# ardusb_zif.net
KiCad netlist of a schematic drawn in EAGLE
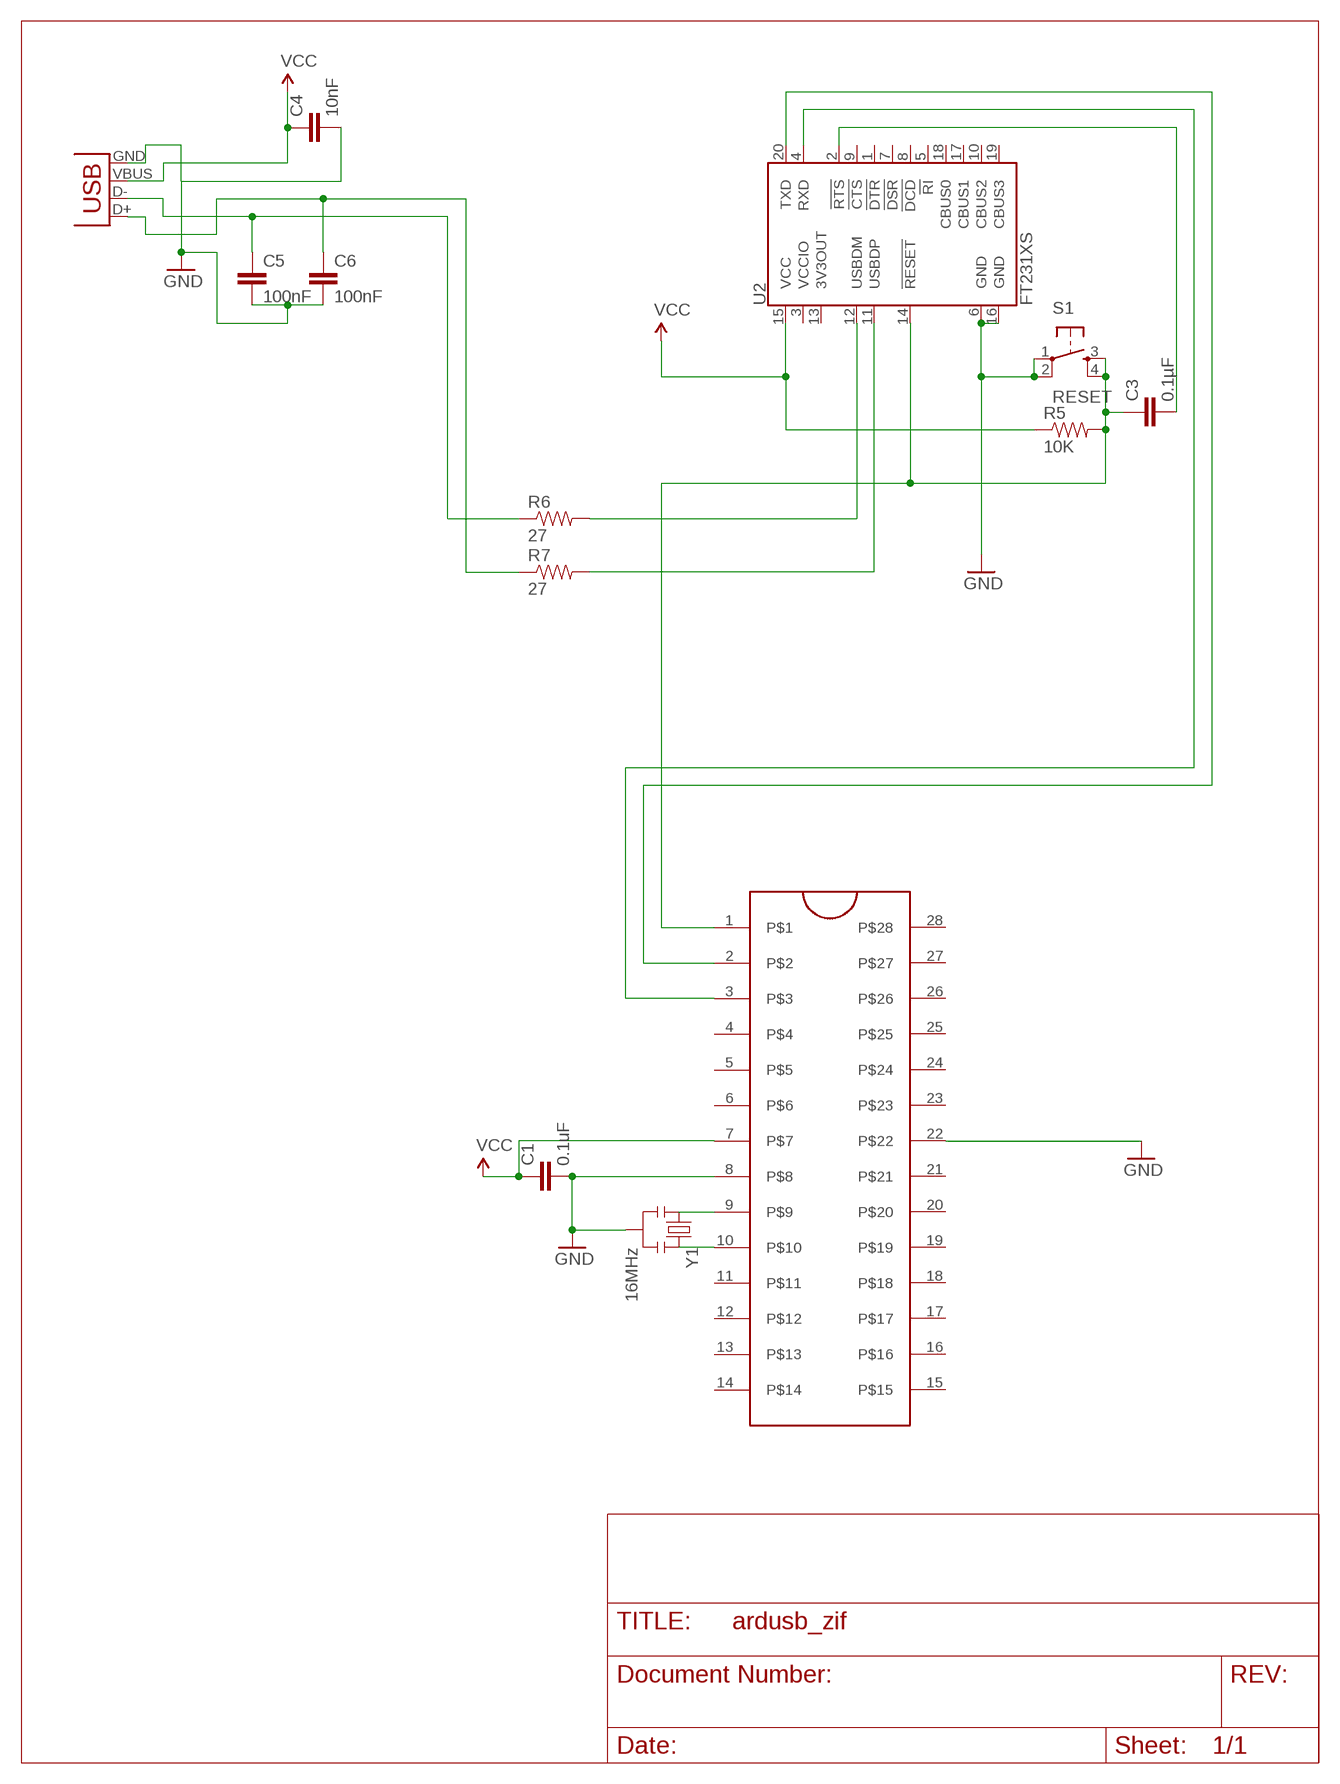
[diagram p0: schematic, sheet 1]

(export (version "E")
  (design (tool "Eeschema 10.0.6"))
  (components
    (comp (ref "C1")
      (value "0.1uF")
      (footprint "eagle-import:CAP-PTH-SMALL")
      (libsource (lib "eagle-import") (part "CAPPTH"))
    )
    (comp (ref "C3")
      (value "0.1µF")
      (footprint "eagle-import:CAP-PTH-SMALL")
      (libsource (lib "eagle-import") (part "SparkFun-Passives_CAPPTH"))
    )
    (comp (ref "C4")
      (value "10nF")
      (footprint "eagle-import:CAP-PTH-SMALL")
      (libsource (lib "eagle-import") (part "SparkFun-Passives_CAPPTH"))
    )
    (comp (ref "C5")
      (value "100nF")
      (footprint "eagle-import:CAP-PTH-SMALL")
      (libsource (lib "eagle-import") (part "CAPPTH"))
    )
    (comp (ref "C6")
      (value "100nF")
      (footprint "eagle-import:CAP-PTH-SMALL")
      (libsource (lib "eagle-import") (part "CAPPTH"))
    )
    (comp (ref "JP1")
      (value "USB-B")
      (footprint "eagle-import:USB-B-PTH")
      (libsource (lib "eagle-import") (part "USBPTH"))
    )
    (comp (ref "R5")
      (value "10K")
      (footprint "eagle-import:AXIAL-0.6")
      (libsource (lib "eagle-import") (part "RESISTORPTH-1W"))
    )
    (comp (ref "R6")
      (value "27")
      (footprint "eagle-import:AXIAL-0.6")
      (libsource (lib "eagle-import") (part "RESISTORPTH-1W"))
    )
    (comp (ref "R7")
      (value "27")
      (footprint "eagle-import:AXIAL-0.6")
      (libsource (lib "eagle-import") (part "RESISTORPTH-1W"))
    )
    (comp (ref "S1")
      (value "RESET")
      (footprint "eagle-import:TACTILE-PTH")
      (libsource (lib "eagle-import") (part "TAC_SWITCHPTH"))
    )
    (comp (ref "U$1")
      (value "ZIFSOCKET-28-3ZIFFSOCKET-28-3")
      (footprint "eagle-import:DIL28-3-ZIF_SOCKET")
      (libsource (lib "eagle-import") (part "ZIFSOCKET-28-3ZIFFSOCKET-28-3"))
    )
    (comp (ref "U2")
      (value "FT231XS")
      (footprint "eagle-import:SSOP20_L")
      (libsource (lib "eagle-import") (part "FT231XS"))
    )
    (comp (ref "Y1")
      (value "16MHz")
      (footprint "eagle-import:RESONATOR-PTH")
      (libsource (lib "eagle-import") (part "RESONATORPTH"))
    )
  )
  (nets
    (net (code "1") (name "GND") (class "Default")
      (node (ref "C1") (pin "2") (pinfunction "2_2") (pintype "passive"))
      (node (ref "C4") (pin "2") (pinfunction "2_2") (pintype "passive"))
      (node (ref "C5") (pin "2") (pinfunction "2_2") (pintype "passive"))
      (node (ref "C6") (pin "2") (pinfunction "2_2") (pintype "passive"))
      (node (ref "JP1") (pin "GND") (pinfunction "GND_GND") (pintype "bidirectional"))
      (node (ref "S1") (pin "1") (pinfunction "1_1") (pintype "passive"))
      (node (ref "S1") (pin "2") (pinfunction "2_2") (pintype "passive"))
      (node (ref "U$1") (pin "22") (pinfunction "P$22_22") (pintype "bidirectional"))
      (node (ref "U$1") (pin "8") (pinfunction "P$8_8") (pintype "bidirectional"))
      (node (ref "U2") (pin "16") (pinfunction "GND_16") (pintype "bidirectional"))
      (node (ref "U2") (pin "6") (pinfunction "GND_6") (pintype "bidirectional"))
      (node (ref "Y1") (pin "2") (pinfunction "2_2") (pintype "passive"))
    )
    (net (code "2") (name "Net-(R5-2)") (class "Default")
      (node (ref "C3") (pin "1") (pinfunction "1_1") (pintype "passive"))
      (node (ref "R5") (pin "P$2") (pinfunction "2_P$2") (pintype "passive"))
      (node (ref "S1") (pin "3") (pinfunction "3_3") (pintype "passive"))
      (node (ref "S1") (pin "4") (pinfunction "4_4") (pintype "passive"))
      (node (ref "U$1") (pin "1") (pinfunction "P$1_1") (pintype "bidirectional"))
      (node (ref "U2") (pin "14") (pinfunction "~{RESET}_14") (pintype "bidirectional"))
    )
    (net (code "3") (name "Net-(R6-1)") (class "Default")
      (node (ref "C5") (pin "1") (pinfunction "1_1") (pintype "passive"))
      (node (ref "JP1") (pin "D-") (pinfunction "D-_D-") (pintype "bidirectional"))
      (node (ref "R6") (pin "P$1") (pinfunction "1_P$1") (pintype "passive"))
    )
    (net (code "4") (name "Net-(R6-2)") (class "Default")
      (node (ref "R6") (pin "P$2") (pinfunction "2_P$2") (pintype "passive"))
      (node (ref "U2") (pin "12") (pinfunction "USBDM_12") (pintype "bidirectional"))
    )
    (net (code "5") (name "Net-(R7-1)") (class "Default")
      (node (ref "C6") (pin "1") (pinfunction "1_1") (pintype "passive"))
      (node (ref "JP1") (pin "D+") (pinfunction "D+_D+") (pintype "bidirectional"))
      (node (ref "R7") (pin "P$1") (pinfunction "1_P$1") (pintype "passive"))
    )
    (net (code "6") (name "Net-(R7-2)") (class "Default")
      (node (ref "R7") (pin "P$2") (pinfunction "2_P$2") (pintype "passive"))
      (node (ref "U2") (pin "11") (pinfunction "USBDP_11") (pintype "bidirectional"))
    )
    (net (code "7") (name "Net-(U$1-P$2)") (class "Default")
      (node (ref "U$1") (pin "2") (pinfunction "P$2_2") (pintype "bidirectional"))
      (node (ref "U2") (pin "20") (pinfunction "TXD_20") (pintype "bidirectional"))
    )
    (net (code "8") (name "Net-(U$1-P$3)") (class "Default")
      (node (ref "U$1") (pin "3") (pinfunction "P$3_3") (pintype "bidirectional"))
      (node (ref "U2") (pin "4") (pinfunction "RXD_4") (pintype "bidirectional"))
    )
    (net (code "9") (name "Net-(U$1-P$9)") (class "Default")
      (node (ref "U$1") (pin "9") (pinfunction "P$9_9") (pintype "bidirectional"))
      (node (ref "Y1") (pin "1") (pinfunction "1_1") (pintype "passive"))
    )
    (net (code "10") (name "Net-(U$1-P$10)") (class "Default")
      (node (ref "U$1") (pin "10") (pinfunction "P$10_10") (pintype "bidirectional"))
      (node (ref "Y1") (pin "3") (pinfunction "3_3") (pintype "passive"))
    )
    (net (code "11") (name "Net-(U2-~{RTS})") (class "Default")
      (node (ref "C3") (pin "2") (pinfunction "2_2") (pintype "passive"))
      (node (ref "U2") (pin "2") (pinfunction "~{RTS}_2") (pintype "bidirectional"))
    )
    (net (code "12") (name "VCC") (class "Default")
      (node (ref "C1") (pin "1") (pinfunction "1_1") (pintype "passive"))
      (node (ref "C4") (pin "1") (pinfunction "1_1") (pintype "passive"))
      (node (ref "JP1") (pin "VBUS") (pinfunction "VBUS_VBUS") (pintype "bidirectional"))
      (node (ref "R5") (pin "P$1") (pinfunction "1_P$1") (pintype "passive"))
      (node (ref "U$1") (pin "7") (pinfunction "P$7_7") (pintype "bidirectional"))
      (node (ref "U2") (pin "15") (pinfunction "VCC_15") (pintype "bidirectional"))
    )
    (net (code "13") (name "unconnected-(U$1-P$4-Pad4)") (class "Default")
      (node (ref "U$1") (pin "4") (pinfunction "P$4_4") (pintype "bidirectional"))
    )
    (net (code "14") (name "unconnected-(U$1-P$5-Pad5)") (class "Default")
      (node (ref "U$1") (pin "5") (pinfunction "P$5_5") (pintype "bidirectional"))
    )
    (net (code "15") (name "unconnected-(U$1-P$6-Pad6)") (class "Default")
      (node (ref "U$1") (pin "6") (pinfunction "P$6_6") (pintype "bidirectional"))
    )
    (net (code "16") (name "unconnected-(U$1-P$11-Pad11)") (class "Default")
      (node (ref "U$1") (pin "11") (pinfunction "P$11_11") (pintype "bidirectional"))
    )
    (net (code "17") (name "unconnected-(U$1-P$12-Pad12)") (class "Default")
      (node (ref "U$1") (pin "12") (pinfunction "P$12_12") (pintype "bidirectional"))
    )
    (net (code "18") (name "unconnected-(U$1-P$13-Pad13)") (class "Default")
      (node (ref "U$1") (pin "13") (pinfunction "P$13_13") (pintype "bidirectional"))
    )
    (net (code "19") (name "unconnected-(U$1-P$14-Pad14)") (class "Default")
      (node (ref "U$1") (pin "14") (pinfunction "P$14_14") (pintype "bidirectional"))
    )
    (net (code "20") (name "unconnected-(U$1-P$15-Pad15)") (class "Default")
      (node (ref "U$1") (pin "15") (pinfunction "P$15_15") (pintype "bidirectional"))
    )
    (net (code "21") (name "unconnected-(U$1-P$16-Pad16)") (class "Default")
      (node (ref "U$1") (pin "16") (pinfunction "P$16_16") (pintype "bidirectional"))
    )
    (net (code "22") (name "unconnected-(U$1-P$17-Pad17)") (class "Default")
      (node (ref "U$1") (pin "17") (pinfunction "P$17_17") (pintype "bidirectional"))
    )
    (net (code "23") (name "unconnected-(U$1-P$18-Pad18)") (class "Default")
      (node (ref "U$1") (pin "18") (pinfunction "P$18_18") (pintype "bidirectional"))
    )
    (net (code "24") (name "unconnected-(U$1-P$19-Pad19)") (class "Default")
      (node (ref "U$1") (pin "19") (pinfunction "P$19_19") (pintype "bidirectional"))
    )
    (net (code "25") (name "unconnected-(U$1-P$20-Pad20)") (class "Default")
      (node (ref "U$1") (pin "20") (pinfunction "P$20_20") (pintype "bidirectional"))
    )
    (net (code "26") (name "unconnected-(U$1-P$21-Pad21)") (class "Default")
      (node (ref "U$1") (pin "21") (pinfunction "P$21_21") (pintype "bidirectional"))
    )
    (net (code "27") (name "unconnected-(U$1-P$23-Pad23)") (class "Default")
      (node (ref "U$1") (pin "23") (pinfunction "P$23_23") (pintype "bidirectional"))
    )
    (net (code "28") (name "unconnected-(U$1-P$24-Pad24)") (class "Default")
      (node (ref "U$1") (pin "24") (pinfunction "P$24_24") (pintype "bidirectional"))
    )
    (net (code "29") (name "unconnected-(U$1-P$25-Pad25)") (class "Default")
      (node (ref "U$1") (pin "25") (pinfunction "P$25_25") (pintype "bidirectional"))
    )
    (net (code "30") (name "unconnected-(U$1-P$26-Pad26)") (class "Default")
      (node (ref "U$1") (pin "26") (pinfunction "P$26_26") (pintype "bidirectional"))
    )
    (net (code "31") (name "unconnected-(U$1-P$27-Pad27)") (class "Default")
      (node (ref "U$1") (pin "27") (pinfunction "P$27_27") (pintype "bidirectional"))
    )
    (net (code "32") (name "unconnected-(U$1-P$28-Pad28)") (class "Default")
      (node (ref "U$1") (pin "28") (pinfunction "P$28_28") (pintype "bidirectional"))
    )
    (net (code "33") (name "unconnected-(U2-3V3OUT-Pad13)") (class "Default")
      (node (ref "U2") (pin "13") (pinfunction "3V3OUT_13") (pintype "bidirectional"))
    )
    (net (code "34") (name "unconnected-(U2-CBUS0-Pad18)") (class "Default")
      (node (ref "U2") (pin "18") (pinfunction "CBUS0_18") (pintype "bidirectional"))
    )
    (net (code "35") (name "unconnected-(U2-CBUS1-Pad17)") (class "Default")
      (node (ref "U2") (pin "17") (pinfunction "CBUS1_17") (pintype "bidirectional"))
    )
    (net (code "36") (name "unconnected-(U2-CBUS2-Pad10)") (class "Default")
      (node (ref "U2") (pin "10") (pinfunction "CBUS2_10") (pintype "bidirectional"))
    )
    (net (code "37") (name "unconnected-(U2-CBUS3-Pad19)") (class "Default")
      (node (ref "U2") (pin "19") (pinfunction "CBUS3_19") (pintype "bidirectional"))
    )
    (net (code "38") (name "unconnected-(U2-VCCIO-Pad3)") (class "Default")
      (node (ref "U2") (pin "3") (pinfunction "VCCIO_3") (pintype "bidirectional"))
    )
    (net (code "39") (name "unconnected-(U2-~{CTS}-Pad9)") (class "Default")
      (node (ref "U2") (pin "9") (pinfunction "~{CTS}_9") (pintype "bidirectional"))
    )
    (net (code "40") (name "unconnected-(U2-~{DCD}-Pad8)") (class "Default")
      (node (ref "U2") (pin "8") (pinfunction "~{DCD}_8") (pintype "bidirectional"))
    )
    (net (code "41") (name "unconnected-(U2-~{DSR}-Pad7)") (class "Default")
      (node (ref "U2") (pin "7") (pinfunction "~{DSR}_7") (pintype "bidirectional"))
    )
    (net (code "42") (name "unconnected-(U2-~{DTR}-Pad1)") (class "Default")
      (node (ref "U2") (pin "1") (pinfunction "~{DTR}_1") (pintype "bidirectional"))
    )
    (net (code "43") (name "unconnected-(U2-~{RI}-Pad5)") (class "Default")
      (node (ref "U2") (pin "5") (pinfunction "~{RI}_5") (pintype "bidirectional"))
    )
  )
)
